# TEST-GPS_RF-REV-C.net
KiCad netlist of a schematic drawn in Altium Designer
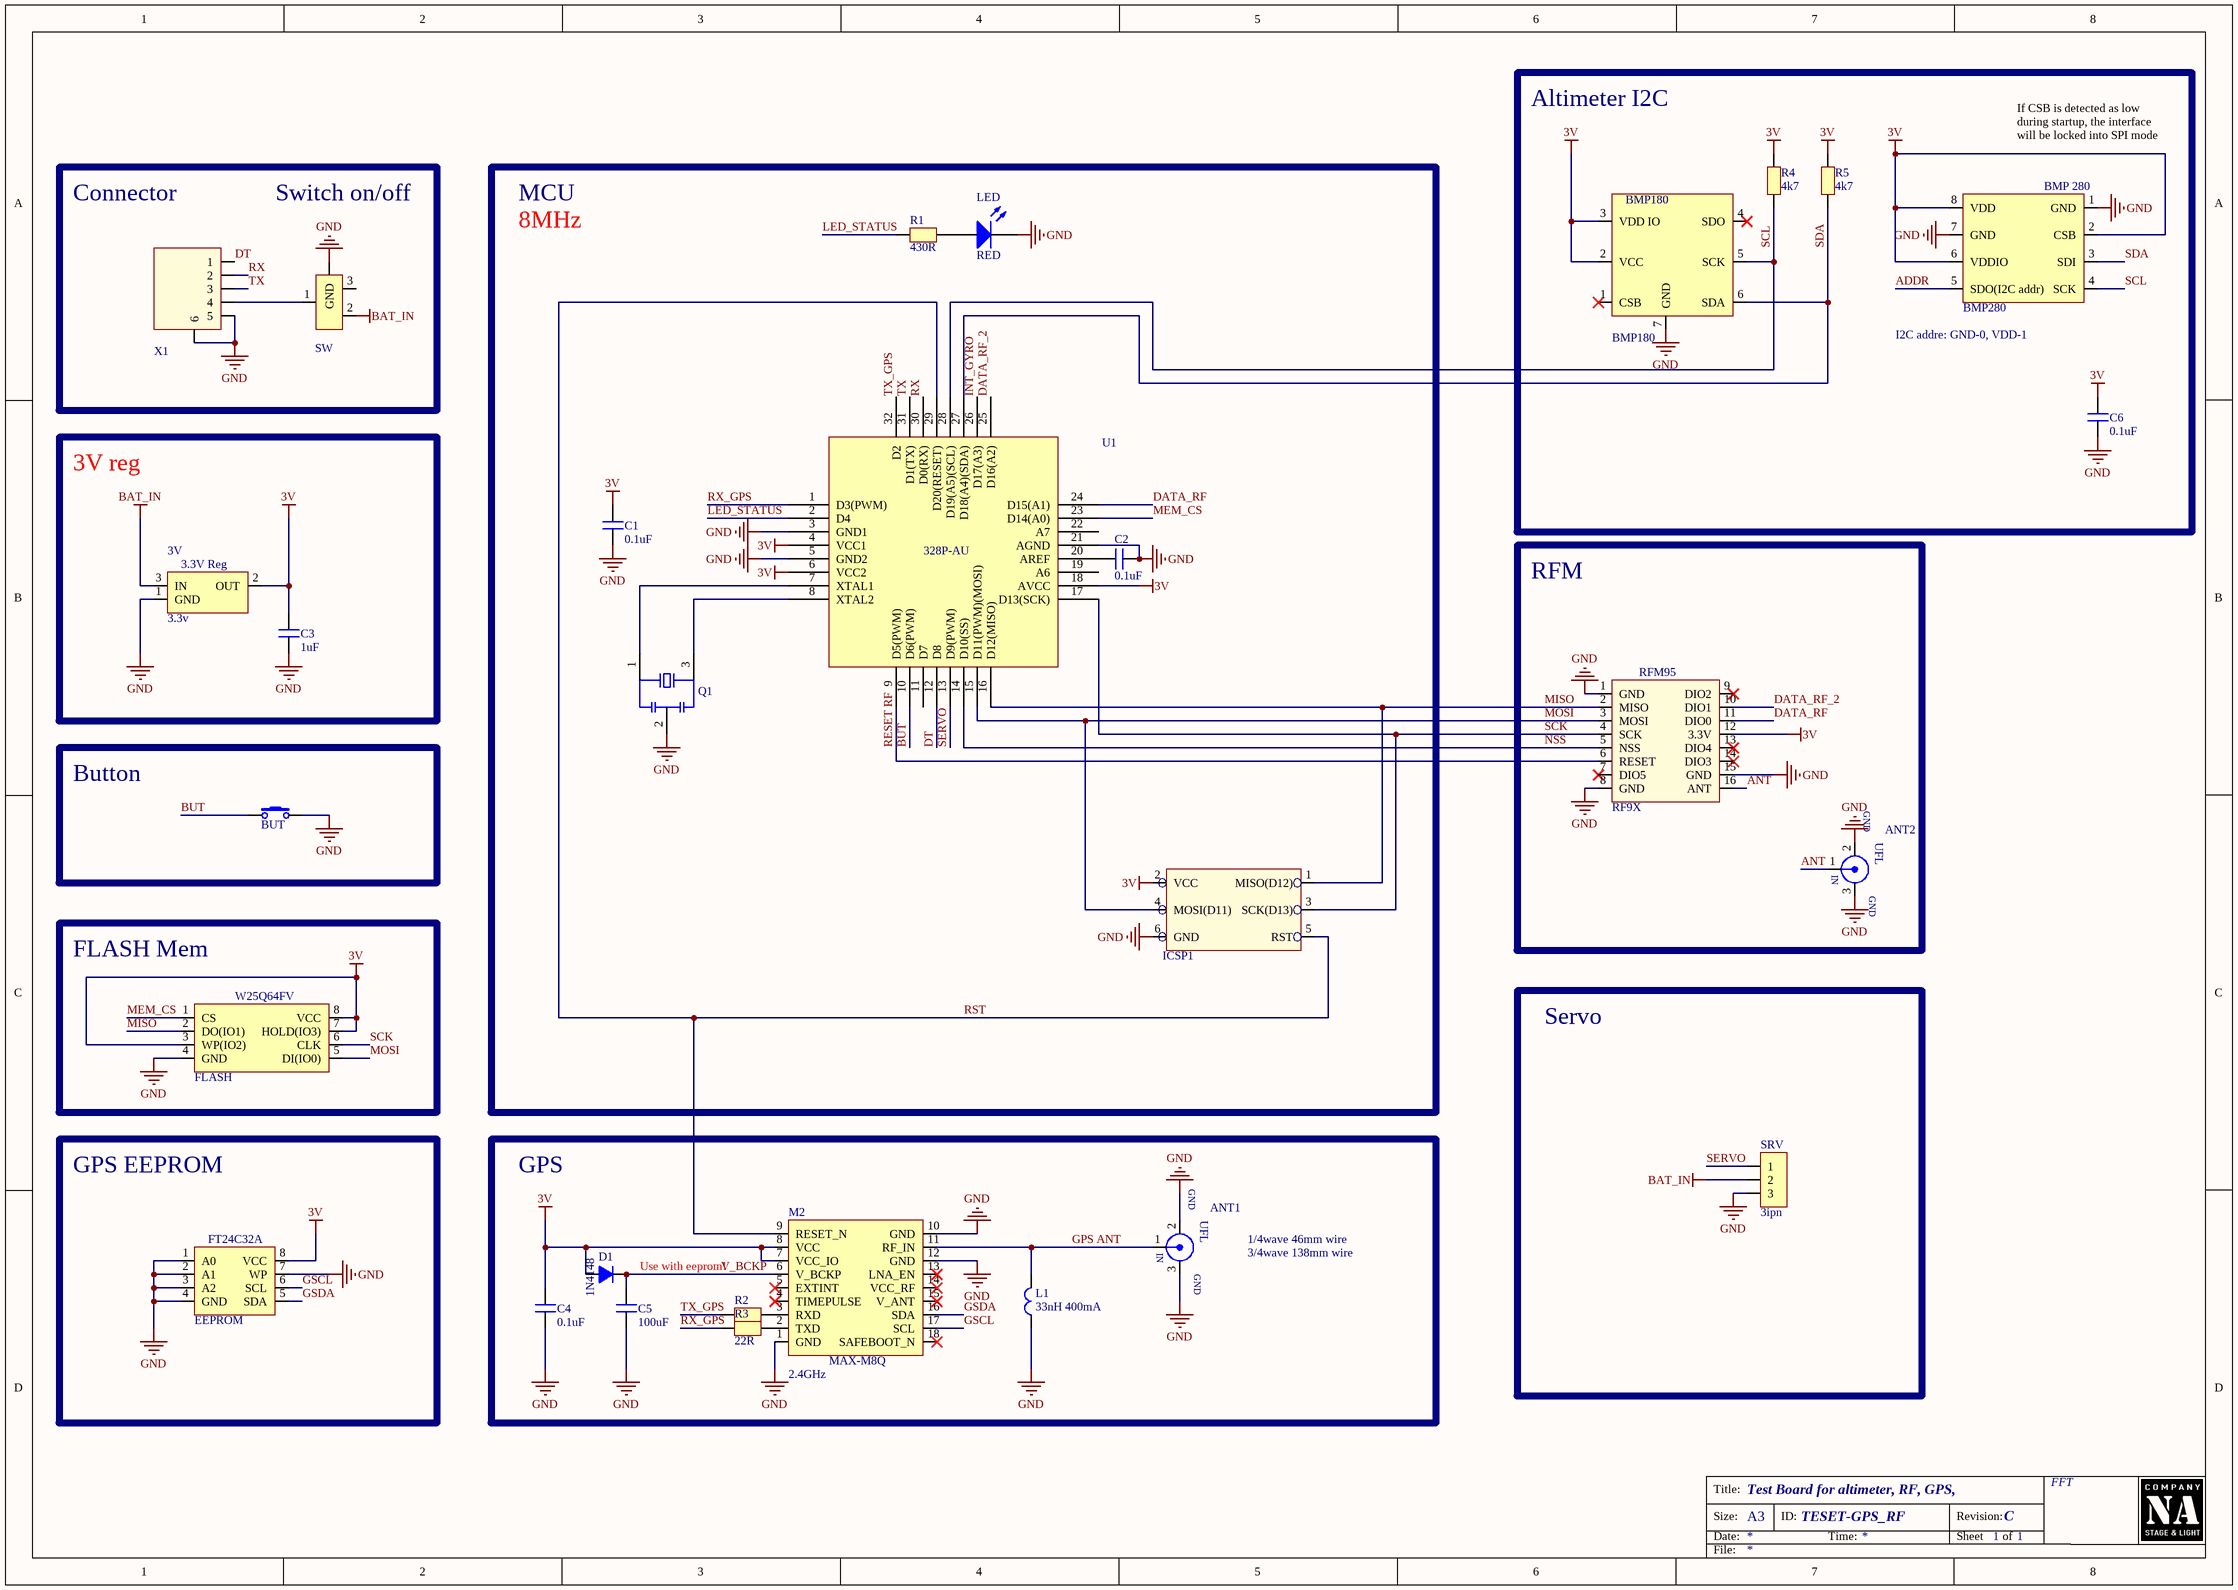
[diagram p0: TEST-GPS_RF-REV-C.SchDoc]

(export (version "E")
  (design (tool "Eeschema 10.0.6"))
  (components
    (comp (ref "3V")
      (value "3.3v")
      (footprint "SOT23-3")
      (description "LDO 3.3V 200mA")
      (fields (field (name "PART NUMBER") "XC6206P332MR") (field (name "MANUFACTURER") "TOREX"))
      (libsource (lib "LCSC") (part "XC6206P332MR"))
    )
    (comp (ref "ANT1")
      (value "UFL-simple")
      (footprint "UFL")
      (description "Connector")
      (fields (field (name "MANUFACTURER") "Aliexpress") (field (name "PART NUMBER") "123123"))
      (libsource (lib "FFT") (part "UFL - simple"))
    )
    (comp (ref "ANT2")
      (value "UFL-simple")
      (footprint "UFL")
      (description "Connector")
      (fields (field (name "MANUFACTURER") "Aliexpress") (field (name "PART NUMBER") "123123"))
      (libsource (lib "FFT") (part "UFL - simple"))
    )
    (comp (ref "BMP180")
      (value "± 0.12 hPa equivalent to ±1 m")
      (footprint "BMP180")
      (description "Pressure sensor BMP 180")
      (fields (field (name "MANUFACTURER") "BOSCH") (field (name "PART NUMBER") "BMP 180"))
      (libsource (lib "My_Storage") (part "BMP 180"))
    )
    (comp (ref "BMP280")
      (value "± 0.12 hPa equivalent to ±1 m")
      (footprint "BMP280")
      (description "Pressure sensor BMP 280")
      (fields (field (name "MANUFACTURER") "BOSCH") (field (name "PART NUMBER") "828-1064-1-ND - BMP 280"))
      (libsource (lib "My_Storage") (part "BMP 280"))
    )
    (comp (ref "BUT")
      (value "B3S-1002")
      (footprint "B3S-1002 FFT")
      (description "Single pole tactile switch, H=4.2mm")
      (fields (field (name "MANUFACTURER") "Omron"))
      (libsource (lib "FFT") (part "B3S-1002"))
    )
    (comp (ref "C1")
      (value "0.1uF")
      (footprint "Capacitor:C0603")
      (description "C0603_0.1uF_50V")
      (fields (field (name "PART NUMBER") "CL10B104KB8NNNC") (field (name "MANUFACTURER") "SAMSUNG"))
      (libsource (lib "Capacitor") (part "C0603_0.1uF_50V"))
    )
    (comp (ref "C2")
      (value "0.1uF")
      (footprint "Capacitor:C0603")
      (description "C0603_0.1uF_50V")
      (fields (field (name "PART NUMBER") "CL10B104KB8NNNC") (field (name "MANUFACTURER") "SAMSUNG"))
      (libsource (lib "Capacitor") (part "C0603_0.1uF_50V"))
    )
    (comp (ref "C3")
      (value "1uF")
      (footprint "Capacitor:C0603")
      (description "C0603_1uF_10V")
      (fields (field (name "PART NUMBER") "CL10A105KP8NNNC") (field (name "MANUFACTURER") "SAMSUNG"))
      (libsource (lib "Capacitor") (part "C0603_1uF_10V"))
    )
    (comp (ref "C4")
      (value "0.1uF")
      (footprint "Capacitor:C0603")
      (description "C0603_0.1uF_50V")
      (fields (field (name "PART NUMBER") "CL10B104KB8NNNC") (field (name "MANUFACTURER") "SAMSUNG"))
      (libsource (lib "Capacitor") (part "C0603_0.1uF_50V"))
    )
    (comp (ref "C5")
      (value "100uF")
      (footprint "Capacitor:C1210")
      (description "C1210_10uF_250V")
      (fields (field (name "PART NUMBER") "CL32A107MPVNNNE") (field (name "MANUFACTURER") "Samsung"))
      (libsource (lib "FFT") (part "C1210_100uF_250V"))
    )
    (comp (ref "C6")
      (value "0.1uF")
      (footprint "Capacitor:C0603")
      (description "C0603_0.1uF_50V")
      (fields (field (name "PART NUMBER") "CL10B104KB8NNNC") (field (name "MANUFACTURER") "SAMSUNG"))
      (libsource (lib "Capacitor") (part "C0603_0.1uF_50V"))
    )
    (comp (ref "D1")
      (value "1N4148")
      (footprint "Semiconductor:SOD-323")
      (description "Small signal diode")
      (fields (field (name "PART NUMBER") "1N4148WS-7-F") (field (name "MANUFACTURER") "Diodes Incorporated"))
      (libsource (lib "LCSC") (part "1N4148WS-7-F"))
    )
    (comp (ref "EEPROM")
      (value "32KBit")
      (footprint "TSSOP - 8")
      (description "Memory EEPROM for GPS")
      (fields (field (name "MANUFACTURER") "FMD") (field (name "PART NUMBER") "FT24C32A-ETR-T"))
      (libsource (lib "LCSC") (part "FT24C32A"))
    )
    (comp (ref "FLASH")
      (value "-")
      (footprint "VSOP8")
      (description "Memory Flash SPI 64MBit")
      (fields (field (name "MANUFACTURER") "Windbond") (field (name "PART NUMBER") "W25Q64FV"))
      (libsource (lib "My_Storage") (part "W25Q64FV"))
    )
    (comp (ref "ICSP1")
      (value "Progr ICSP")
      (footprint "ICSP prg PAD 2.54mm")
      (description "PAD prog")
      (libsource (lib "FFT") (part "Progr ICSP"))
    )
    (comp (ref "L1")
      (value "33nH 400mA")
      (footprint "L0603")
      (description "Inductor")
      (fields (field (name "PART NUMBER") "744786133A") (field (name "MANUFACTURER") "Murata"))
      (libsource (lib "FFT") (part "L0603_33nH"))
    )
    (comp (ref "LED")
      (value "RED")
      (footprint "LED0603")
      (description "LED 0603 chip")
      (fields (field (name "MANUFACTURER") "Hubei KENTO Elec") (field (name "PART NUMBER") "KT-0603R"))
      (libsource (lib "My_Storage") (part "KT-0603R"))
    )
    (comp (ref "M2")
      (value "2.4GHz")
      (footprint "MAX-M8Q")
      (description "GPS module")
      (fields (field (name "MANUFACTURER") "uBlox"))
      (libsource (lib "FFT") (part "MAX-M8Q"))
    )
    (comp (ref "Q1")
      (value "osc 8Mhz CSTCE8M0V53-R0_1")
      (footprint "OSC_CSTCE16M0V53-R0")
      (description "8MHz Ceramic Resonator Built in Cap 15pF ±0.3% -20°C ~ 80°C SMD")
      (fields (field (name "MANUFACTURER") "Murata") (field (name "PART NUMBER") "CSTCE8M0V53-R0_1"))
      (libsource (lib "My_Storage") (part "osc 8Mhz CSTCE8M0V53-R0_1"))
    )
    (comp (ref "R1")
      (value "430R")
      (footprint "Resistor:0603")
      (description "SMD resistor")
      (fields (field (name "PART NUMBER") "RC0603FR-07430RL") (field (name "MANUFACTURER") "Yageo"))
      (libsource (lib "Resistor") (part "R0603_430"))
    )
    (comp (ref "R2")
      (value "22R")
      (footprint "Resistor:0603")
      (description "SMD resistor")
      (fields (field (name "PART NUMBER") "CRCW060322R0FKTABC") (field (name "MANUFACTURER") "VISHAY"))
      (libsource (lib "Resistor") (part "R0603_22"))
    )
    (comp (ref "R3")
      (value "22R")
      (footprint "Resistor:0603")
      (description "SMD resistor")
      (fields (field (name "PART NUMBER") "CRCW060322R0FKTABC") (field (name "MANUFACTURER") "VISHAY"))
      (libsource (lib "Resistor") (part "R0603_22"))
    )
    (comp (ref "R4")
      (value "4k7")
      (footprint "Resistor:0603")
      (description "SMD resistor")
      (fields (field (name "PART NUMBER") "SMD0603-4K7-1%") (field (name "MANUFACTURER") "Yageo"))
      (libsource (lib "Resistor") (part "R0603_4k7"))
    )
    (comp (ref "R5")
      (value "4k7")
      (footprint "Resistor:0603")
      (description "SMD resistor")
      (fields (field (name "PART NUMBER") "SMD0603-4K7-1%") (field (name "MANUFACTURER") "Yageo"))
      (libsource (lib "Resistor") (part "R0603_4k7"))
    )
    (comp (ref "RF9X")
      (value "RFM95")
      (footprint "RFM9x")
      (description "RF Transceiver")
      (fields (field (name "MANUFACTURER") "Hope RF Electronics"))
      (libsource (lib "FFT") (part "RFM95"))
    )
    (comp (ref "SRV")
      (value "3ipn")
      (footprint "HDR1x3 angled")
      (description "Header 3-Pin, 2.54mm")
      (fields (field (name "MANUFACTURER") "Connfly") (field (name "PART NUMBER") "DS1021-1*3SF1-1"))
      (libsource (lib "FFT") (part "Header 3x1"))
    )
    (comp (ref "SW")
      (value "~")
      (footprint "Switch slide")
      (description "Switch")
      (fields (field (name "MANUFACTURER") "Xiejia") (field (name "PART NUMBER") "MK12C02"))
      (libsource (lib "FFT") (part "MK12C02"))
    )
    (comp (ref "U1")
      (value "~")
      (footprint "32-pin QFP 10mm")
      (description "CPU")
      (fields (field (name "PART NUMBER") "ATmega 328p-AU") (field (name "MANUFACTURER") "TI"))
      (libsource (lib "FFT") (part "328p-AU-arduino"))
    )
    (comp (ref "X1")
      (value "1.0mm 5pin")
      (footprint "JST 5pin 1mm")
      (description "Connector 5p hor 1mm")
      (fields (field (name "MANUFACTURER") "JST") (field (name "PART NUMBER") "SM05B-SRSS-TB"))
      (libsource (lib "FFT") (part "SM05B-SRSS-TB"))
    )
  )
  (nets
    (net (code "1") (name "/ADDR") (class "Default")
      (node (ref "BMP280") (pin "5") (pinfunction "SDO(I2C_addr)_5") (pintype "passive"))
    )
    (net (code "2") (name "/ANT") (class "Default")
      (node (ref "ANT2") (pin "1") (pinfunction "ANT_1") (pintype "passive"))
      (node (ref "RF9X") (pin "16") (pinfunction "ANT_16") (pintype "passive"))
    )
    (net (code "3") (name "/BUT") (class "Default")
      (node (ref "BUT") (pin "2") (pinfunction "2_2") (pintype "passive"))
      (node (ref "U1") (pin "10") (pinfunction "D6(PWM)_10") (pintype "passive"))
    )
    (net (code "4") (name "/DATA_RF") (class "Default")
      (node (ref "RF9X") (pin "11") (pinfunction "DIO0_11") (pintype "passive"))
      (node (ref "U1") (pin "24") (pinfunction "D15(A1)_24") (pintype "passive"))
    )
    (net (code "5") (name "/DATA_RF_2") (class "Default")
      (node (ref "RF9X") (pin "10") (pinfunction "DIO1_10") (pintype "passive"))
      (node (ref "U1") (pin "25") (pinfunction "D16(A2)_25") (pintype "passive"))
    )
    (net (code "6") (name "/DT") (class "Default")
      (node (ref "U1") (pin "12") (pinfunction "D8_12") (pintype "passive"))
      (node (ref "X1") (pin "1") (pinfunction "1_1") (pintype "passive"))
    )
    (net (code "7") (name "/GPS ANT") (class "Default")
      (node (ref "ANT1") (pin "1") (pinfunction "ANT_1") (pintype "passive"))
      (node (ref "L1") (pin "2") (pinfunction "2_2") (pintype "passive"))
      (node (ref "M2") (pin "11") (pinfunction "RF_IN_11") (pintype "passive"))
    )
    (net (code "8") (name "/GSCL") (class "Default")
      (node (ref "EEPROM") (pin "6") (pinfunction "SCL_6") (pintype "passive"))
      (node (ref "M2") (pin "17") (pinfunction "SCL_17") (pintype "passive"))
    )
    (net (code "9") (name "/GSDA") (class "Default")
      (node (ref "EEPROM") (pin "5") (pinfunction "SDA_5") (pintype "passive"))
      (node (ref "M2") (pin "16") (pinfunction "SDA_16") (pintype "passive"))
    )
    (net (code "10") (name "/INT_GYRO") (class "Default")
      (node (ref "U1") (pin "26") (pinfunction "D17(A3)_26") (pintype "passive"))
    )
    (net (code "11") (name "/LED_STATUS") (class "Default")
      (node (ref "R1") (pin "1") (pinfunction "1_1") (pintype "passive"))
      (node (ref "U1") (pin "2") (pinfunction "D4_2") (pintype "passive"))
    )
    (net (code "12") (name "/MEM_CS") (class "Default")
      (node (ref "FLASH") (pin "1") (pinfunction "CS_1") (pintype "passive"))
      (node (ref "U1") (pin "23") (pinfunction "D14(A0)_23") (pintype "passive"))
    )
    (net (code "13") (name "/MISO") (class "Default")
      (node (ref "FLASH") (pin "2") (pinfunction "DO(IO1)_2") (pintype "passive"))
      (node (ref "ICSP1") (pin "1") (pinfunction "MISO(D12)_1") (pintype "passive"))
      (node (ref "RF9X") (pin "2") (pinfunction "MISO_2") (pintype "passive"))
      (node (ref "U1") (pin "16") (pinfunction "D12(MISO)_16") (pintype "passive"))
    )
    (net (code "14") (name "/MOSI") (class "Default")
      (node (ref "FLASH") (pin "5") (pinfunction "DI(IO0)_5") (pintype "passive"))
      (node (ref "ICSP1") (pin "4") (pinfunction "MOSI(D11)_4") (pintype "passive"))
      (node (ref "RF9X") (pin "3") (pinfunction "MOSI_3") (pintype "passive"))
      (node (ref "U1") (pin "15") (pinfunction "D11(PWM)(MOSI)_15") (pintype "passive"))
    )
    (net (code "15") (name "/NSS") (class "Default")
      (node (ref "RF9X") (pin "5") (pinfunction "NSS_5") (pintype "passive"))
      (node (ref "U1") (pin "14") (pinfunction "D10(SS)_14") (pintype "passive"))
    )
    (net (code "16") (name "/RESET RF") (class "Default")
      (node (ref "RF9X") (pin "6") (pinfunction "RESET_6") (pintype "passive"))
      (node (ref "U1") (pin "9") (pinfunction "D5(PWM)_9") (pintype "passive"))
    )
    (net (code "17") (name "/RST") (class "Default")
      (node (ref "ICSP1") (pin "5") (pinfunction "RST_5") (pintype "passive"))
      (node (ref "M2") (pin "9") (pinfunction "RESET_N_9") (pintype "passive"))
      (node (ref "U1") (pin "29") (pinfunction "D20(RESET)_29") (pintype "passive"))
    )
    (net (code "18") (name "/RX") (class "Default")
      (node (ref "U1") (pin "30") (pinfunction "D0(RX)_30") (pintype "passive"))
      (node (ref "X1") (pin "2") (pinfunction "2_2") (pintype "passive"))
    )
    (net (code "19") (name "/RX_GPS") (class "Default")
      (node (ref "R3") (pin "1") (pinfunction "1_1") (pintype "passive"))
      (node (ref "U1") (pin "1") (pinfunction "D3(PWM)_1") (pintype "passive"))
    )
    (net (code "20") (name "/SCK") (class "Default")
      (node (ref "FLASH") (pin "6") (pinfunction "CLK_6") (pintype "passive"))
      (node (ref "ICSP1") (pin "3") (pinfunction "SCK(D13)_3") (pintype "passive"))
      (node (ref "RF9X") (pin "4") (pinfunction "SCK_4") (pintype "passive"))
      (node (ref "U1") (pin "17") (pinfunction "D13(SCK)_17") (pintype "passive"))
    )
    (net (code "21") (name "/SCL") (class "Default")
      (node (ref "BMP180") (pin "5") (pinfunction "SCK_5") (pintype "passive"))
      (node (ref "BMP280") (pin "4") (pinfunction "SCK_4") (pintype "passive"))
      (node (ref "R4") (pin "1") (pinfunction "1_1") (pintype "passive"))
      (node (ref "U1") (pin "28") (pinfunction "D19(A5)(SCL)_28") (pintype "passive"))
    )
    (net (code "22") (name "/SDA") (class "Default")
      (node (ref "BMP180") (pin "6") (pinfunction "SDA_6") (pintype "passive"))
      (node (ref "BMP280") (pin "3") (pinfunction "SDI_3") (pintype "passive"))
      (node (ref "R5") (pin "1") (pinfunction "1_1") (pintype "passive"))
      (node (ref "U1") (pin "27") (pinfunction "D18(A4)(SDA)_27") (pintype "passive"))
    )
    (net (code "23") (name "/SERVO") (class "Default")
      (node (ref "SRV") (pin "1") (pinfunction "1_1") (pintype "passive"))
      (node (ref "U1") (pin "13") (pinfunction "D9(PWM)_13") (pintype "passive"))
    )
    (net (code "24") (name "/TX") (class "Default")
      (node (ref "U1") (pin "31") (pinfunction "D1(TX)_31") (pintype "passive"))
      (node (ref "X1") (pin "3") (pinfunction "3_3") (pintype "passive"))
    )
    (net (code "25") (name "/TX_GPS") (class "Default")
      (node (ref "R2") (pin "1") (pinfunction "1_1") (pintype "passive"))
      (node (ref "U1") (pin "32") (pinfunction "D2_32") (pintype "passive"))
    )
    (net (code "26") (name "/V_BCKP") (class "Default")
      (node (ref "C5") (pin "1") (pintype "passive"))
      (node (ref "D1") (pin "K") (pinfunction "K_K") (pintype "passive"))
      (node (ref "M2") (pin "6") (pinfunction "V_BCKP_6") (pintype "passive"))
    )
    (net (code "27") (name "3V") (class "Default")
      (node (ref "3V") (pin "2") (pinfunction "OUT_2") (pintype "passive"))
      (node (ref "BMP180") (pin "2") (pinfunction "VCC_2") (pintype "passive"))
      (node (ref "BMP180") (pin "3") (pinfunction "VDD_IO_3") (pintype "passive"))
      (node (ref "BMP280") (pin "2") (pinfunction "CSB_2") (pintype "passive"))
      (node (ref "BMP280") (pin "6") (pinfunction "VDDIO_6") (pintype "passive"))
      (node (ref "BMP280") (pin "8") (pinfunction "VDD_8") (pintype "passive"))
      (node (ref "C1") (pin "2") (pintype "passive"))
      (node (ref "C3") (pin "2") (pintype "passive"))
      (node (ref "C4") (pin "1") (pintype "passive"))
      (node (ref "C6") (pin "2") (pintype "passive"))
      (node (ref "D1") (pin "A") (pinfunction "A_A") (pintype "passive"))
      (node (ref "EEPROM") (pin "8") (pinfunction "VCC_8") (pintype "passive"))
      (node (ref "FLASH") (pin "3") (pinfunction "WP(IO2)_3") (pintype "passive"))
      (node (ref "FLASH") (pin "7") (pinfunction "HOLD(IO3)_7") (pintype "passive"))
      (node (ref "FLASH") (pin "8") (pinfunction "VCC_8") (pintype "passive"))
      (node (ref "ICSP1") (pin "2") (pinfunction "VCC_2") (pintype "passive"))
      (node (ref "M2") (pin "7") (pinfunction "VCC_IO_7") (pintype "passive"))
      (node (ref "M2") (pin "8") (pinfunction "VCC_8") (pintype "passive"))
      (node (ref "R4") (pin "2") (pinfunction "2_2") (pintype "passive"))
      (node (ref "R5") (pin "2") (pinfunction "2_2") (pintype "passive"))
      (node (ref "RF9X") (pin "12") (pinfunction "3.3V_12") (pintype "passive"))
      (node (ref "U1") (pin "18") (pinfunction "AVCC_18") (pintype "passive"))
      (node (ref "U1") (pin "4") (pinfunction "VCC1_4") (pintype "passive"))
      (node (ref "U1") (pin "6") (pinfunction "VCC2_6") (pintype "passive"))
    )
    (net (code "28") (name "BAT_IN") (class "Default")
      (node (ref "3V") (pin "3") (pinfunction "IN_3") (pintype "power_in"))
      (node (ref "SRV") (pin "2") (pinfunction "2_2") (pintype "passive"))
      (node (ref "SW") (pin "2") (pinfunction "2_2") (pintype "passive"))
    )
    (net (code "29") (name "GND") (class "Default")
      (node (ref "3V") (pin "1") (pinfunction "GND_1") (pintype "power_in"))
      (node (ref "ANT1") (pin "2") (pinfunction "OUT_2") (pintype "passive"))
      (node (ref "ANT1") (pin "3") (pinfunction "GND_3") (pintype "passive"))
      (node (ref "ANT2") (pin "2") (pinfunction "OUT_2") (pintype "passive"))
      (node (ref "ANT2") (pin "3") (pinfunction "GND_3") (pintype "passive"))
      (node (ref "BMP180") (pin "7") (pinfunction "GND_7") (pintype "passive"))
      (node (ref "BMP280") (pin "1") (pinfunction "GND_1") (pintype "passive"))
      (node (ref "BMP280") (pin "7") (pinfunction "GND_7") (pintype "passive"))
      (node (ref "BUT") (pin "1") (pinfunction "1_1") (pintype "passive"))
      (node (ref "C1") (pin "1") (pintype "passive"))
      (node (ref "C2") (pin "1") (pintype "passive"))
      (node (ref "C3") (pin "1") (pintype "passive"))
      (node (ref "C4") (pin "2") (pintype "passive"))
      (node (ref "C5") (pin "2") (pintype "passive"))
      (node (ref "C6") (pin "1") (pintype "passive"))
      (node (ref "EEPROM") (pin "1") (pinfunction "A0_1") (pintype "passive"))
      (node (ref "EEPROM") (pin "2") (pinfunction "A1_2") (pintype "passive"))
      (node (ref "EEPROM") (pin "3") (pinfunction "A2_3") (pintype "passive"))
      (node (ref "EEPROM") (pin "4") (pinfunction "GND_4") (pintype "passive"))
      (node (ref "EEPROM") (pin "7") (pinfunction "WP_7") (pintype "passive"))
      (node (ref "FLASH") (pin "4") (pinfunction "GND_4") (pintype "passive"))
      (node (ref "ICSP1") (pin "6") (pinfunction "GND_6") (pintype "passive"))
      (node (ref "L1") (pin "1") (pinfunction "1_1") (pintype "passive"))
      (node (ref "LED") (pin "2") (pinfunction "2_2") (pintype "passive"))
      (node (ref "M2") (pin "1") (pinfunction "GND_1") (pintype "passive"))
      (node (ref "M2") (pin "10") (pinfunction "GND_10") (pintype "passive"))
      (node (ref "M2") (pin "12") (pinfunction "GND_12") (pintype "passive"))
      (node (ref "Q1") (pin "2") (pinfunction "OSC2_2") (pintype "passive"))
      (node (ref "RF9X") (pin "1") (pinfunction "GND_1") (pintype "passive"))
      (node (ref "RF9X") (pin "15") (pinfunction "GND_15") (pintype "passive"))
      (node (ref "RF9X") (pin "8") (pinfunction "GND_8") (pintype "passive"))
      (node (ref "SRV") (pin "3") (pinfunction "3_3") (pintype "passive"))
      (node (ref "SW") (pin "4") (pinfunction "GND_4") (pintype "passive"))
      (node (ref "U1") (pin "21") (pinfunction "AGND_21") (pintype "passive"))
      (node (ref "U1") (pin "3") (pinfunction "GND1_3") (pintype "passive"))
      (node (ref "U1") (pin "5") (pinfunction "GND2_5") (pintype "passive"))
      (node (ref "X1") (pin "5") (pinfunction "5_5") (pintype "passive"))
      (node (ref "X1") (pin "6") (pinfunction "6_6") (pintype "passive"))
    )
    (net (code "30") (name "Net-(LED-Pad1)") (class "Default")
      (node (ref "LED") (pin "1") (pinfunction "1_1") (pintype "passive"))
      (node (ref "R1") (pin "2") (pinfunction "2_2") (pintype "passive"))
    )
    (net (code "31") (name "Net-(M2-RXD)") (class "Default")
      (node (ref "M2") (pin "3") (pinfunction "RXD_3") (pintype "passive"))
      (node (ref "R2") (pin "2") (pinfunction "2_2") (pintype "passive"))
    )
    (net (code "32") (name "Net-(M2-TXD)") (class "Default")
      (node (ref "M2") (pin "2") (pinfunction "TXD_2") (pintype "passive"))
      (node (ref "R3") (pin "2") (pinfunction "2_2") (pintype "passive"))
    )
    (net (code "33") (name "Net-(Q1-OSC1)") (class "Default")
      (node (ref "Q1") (pin "1") (pinfunction "OSC1_1") (pintype "passive"))
      (node (ref "U1") (pin "7") (pinfunction "XTAL1_7") (pintype "passive"))
    )
    (net (code "34") (name "Net-(Q1-OSC3)") (class "Default")
      (node (ref "Q1") (pin "3") (pinfunction "OSC3_3") (pintype "passive"))
      (node (ref "U1") (pin "8") (pinfunction "XTAL2_8") (pintype "passive"))
    )
    (net (code "35") (name "Net-(SW-Pad1)") (class "Default")
      (node (ref "SW") (pin "1") (pinfunction "1_1") (pintype "passive"))
      (node (ref "X1") (pin "4") (pinfunction "4_4") (pintype "passive"))
    )
    (net (code "36") (name "Net-(U1-AREF)") (class "Default")
      (node (ref "C2") (pin "2") (pintype "passive"))
      (node (ref "U1") (pin "20") (pinfunction "AREF_20") (pintype "passive"))
    )
    (net (code "37") (name "unconnected-(BMP180-CSB-Pad1)") (class "Default")
      (node (ref "BMP180") (pin "1") (pinfunction "CSB_1") (pintype "passive+no_connect"))
    )
    (net (code "38") (name "unconnected-(BMP180-SDO-Pad4)") (class "Default")
      (node (ref "BMP180") (pin "4") (pinfunction "SDO_4") (pintype "passive+no_connect"))
    )
    (net (code "39") (name "unconnected-(M2-EXTINT-Pad5)") (class "Default")
      (node (ref "M2") (pin "5") (pinfunction "EXTINT_5") (pintype "passive+no_connect"))
    )
    (net (code "40") (name "unconnected-(M2-LNA_EN-Pad13)") (class "Default")
      (node (ref "M2") (pin "13") (pinfunction "LNA_EN_13") (pintype "passive+no_connect"))
    )
    (net (code "41") (name "unconnected-(M2-SAFEBOOT_N-Pad18)") (class "Default")
      (node (ref "M2") (pin "18") (pinfunction "SAFEBOOT_N_18") (pintype "passive+no_connect"))
    )
    (net (code "42") (name "unconnected-(M2-TIMEPULSE-Pad4)") (class "Default")
      (node (ref "M2") (pin "4") (pinfunction "TIMEPULSE_4") (pintype "passive+no_connect"))
    )
    (net (code "43") (name "unconnected-(M2-VCC_RF-Pad14)") (class "Default")
      (node (ref "M2") (pin "14") (pinfunction "VCC_RF_14") (pintype "passive+no_connect"))
    )
    (net (code "44") (name "unconnected-(M2-V_ANT-Pad15)") (class "Default")
      (node (ref "M2") (pin "15") (pinfunction "V_ANT_15") (pintype "passive+no_connect"))
    )
    (net (code "45") (name "unconnected-(RF9X-DIO2-Pad9)") (class "Default")
      (node (ref "RF9X") (pin "9") (pinfunction "DIO2_9") (pintype "passive+no_connect"))
    )
    (net (code "46") (name "unconnected-(RF9X-DIO3-Pad14)") (class "Default")
      (node (ref "RF9X") (pin "14") (pinfunction "DIO3_14") (pintype "passive+no_connect"))
    )
    (net (code "47") (name "unconnected-(RF9X-DIO4-Pad13)") (class "Default")
      (node (ref "RF9X") (pin "13") (pinfunction "DIO4_13") (pintype "passive+no_connect"))
    )
    (net (code "48") (name "unconnected-(RF9X-DIO5-Pad7)") (class "Default")
      (node (ref "RF9X") (pin "7") (pinfunction "DIO5_7") (pintype "passive+no_connect"))
    )
    (net (code "49") (name "unconnected-(SW-Pad3)") (class "Default")
      (node (ref "SW") (pin "3") (pinfunction "3_3") (pintype "passive"))
    )
    (net (code "50") (name "unconnected-(U1-A6-Pad19)") (class "Default")
      (node (ref "U1") (pin "19") (pinfunction "A6_19") (pintype "passive"))
    )
    (net (code "51") (name "unconnected-(U1-A7-Pad22)") (class "Default")
      (node (ref "U1") (pin "22") (pinfunction "A7_22") (pintype "passive"))
    )
    (net (code "52") (name "unconnected-(U1-D7-Pad11)") (class "Default")
      (node (ref "U1") (pin "11") (pinfunction "D7_11") (pintype "passive"))
    )
  )
)
